# Blinker.net
KiCad netlist of a schematic drawn in Altium Designer
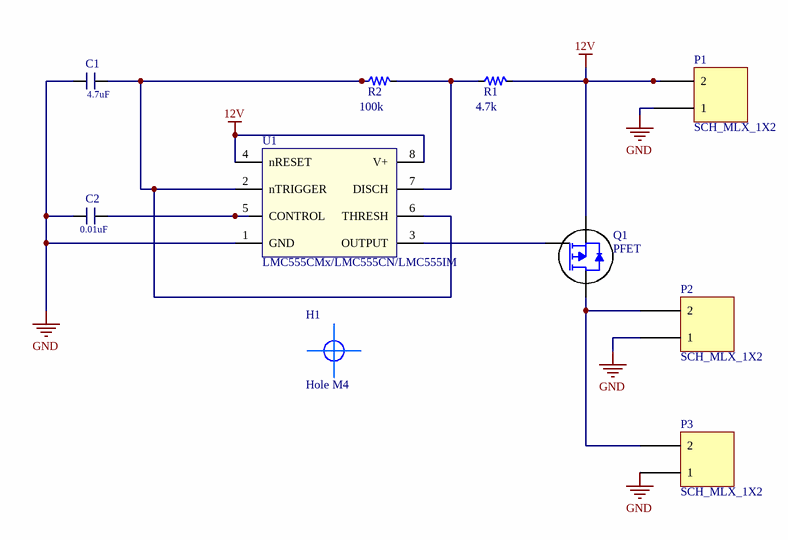
[diagram p0: Blinker.SchDoc]

(export (version "E")
  (design (tool "Eeschema 10.0.6"))
  (components
    (comp (ref "C1")
      (value "SCH_GENERIC_CAPACITOR_0603")
      (footprint "PCB_GENERIC_SMD_0603")
      (description "Generic SMD capacitor 0603")
      (fields (field (name "TOLERANCE") "*%") (field (name "CAPACITANCE") "4.7uF"))
      (libsource (lib "Generic 0603 Capacitor") (part "SCH_GENERIC_CAPACITOR_0603"))
    )
    (comp (ref "C2")
      (value "SCH_GENERIC_CAPACITOR_0603")
      (footprint "PCB_GENERIC_SMD_0603")
      (description "Generic SMD capacitor 0603")
      (fields (field (name "TOLERANCE") "*%") (field (name "CAPACITANCE") "0.01uF"))
      (libsource (lib "Generic 0603 Capacitor") (part "SCH_GENERIC_CAPACITOR_0603"))
    )
    (comp (ref "H1") (value "Hole M4") (footprint "#10Hole") (libsource (lib "#10Hole") (part "#10Hole")))
    (comp (ref "P1")
      (value "SCH_MLX_1X2")
      (footprint "PCB_MLX_MICROFIT_1X2")
      (libsource (lib "Molex Microfit 3.0 1x2") (part "SCH_MLX_1X2"))
    )
    (comp (ref "P2")
      (value "SCH_MLX_1X2")
      (footprint "PCB_MLX_MICROFIT_1X2")
      (libsource (lib "Molex Microfit 3.0 1x2") (part "SCH_MLX_1X2"))
    )
    (comp (ref "P3")
      (value "SCH_MLX_1X2")
      (footprint "PCB_MLX_MICROFIT_1X2")
      (libsource (lib "Molex Microfit 3.0 1x2") (part "SCH_MLX_1X2"))
    )
    (comp (ref "Q1")
      (value "PFET")
      (footprint "SOT23F")
      (description "MOSFET P CH 30V 6A 2-3Z1A")
      (libsource (lib "Blinker") (part "PFET"))
    )
    (comp (ref "R1")
      (value "SCH_GENERIC_RESISTOR_0603")
      (footprint "PCB_GENERIC_SMD_0603")
      (description "Generic SMD resistor 0603")
      (fields (field (name "RESISTANCE") "4.7k"))
      (libsource (lib "Generic 0603 Resistor") (part "SCH_GENERIC_RESISTOR_0603"))
    )
    (comp (ref "R2")
      (value "SCH_GENERIC_RESISTOR_0603")
      (footprint "PCB_GENERIC_SMD_0603")
      (description "Generic SMD resistor 0603")
      (fields (field (name "RESISTANCE") "100k"))
      (libsource (lib "Generic 0603 Resistor") (part "SCH_GENERIC_RESISTOR_0603"))
    )
    (comp (ref "U1")
      (value "LMC555CMx/LMC555CN/LMC555IM")
      (footprint "D-8")
      (description "555 Type, Timer/Oscillator (Single) IC 3MHz 8-SOIC")
      (fields (field (name "PART NUMBER") "LMC555CMX/NOPB") (field (name "MANUFACTURER") "Texas Instruments"))
      (libsource (lib "Blinker") (part "LMC555CMx/LMC555CN/LMC555IM"))
    )
  )
  (nets
    (net (code "1") (name "12V") (class "Default")
      (node (ref "P1") (pin "2") (pinfunction "2_2") (pintype "passive"))
      (node (ref "Q1") (pin "2") (pinfunction "S_2") (pintype "passive"))
      (node (ref "R1") (pin "2") (pinfunction "2_2") (pintype "passive"))
      (node (ref "U1") (pin "4") (pinfunction "nRESET_4") (pintype "passive"))
      (node (ref "U1") (pin "8") (pinfunction "V+_8") (pintype "passive"))
    )
    (net (code "2") (name "GND") (class "Default")
      (node (ref "C1") (pin "1") (pinfunction "1_1") (pintype "passive"))
      (node (ref "C2") (pin "1") (pinfunction "1_1") (pintype "passive"))
      (node (ref "P1") (pin "1") (pinfunction "1_1") (pintype "passive"))
      (node (ref "P2") (pin "1") (pinfunction "1_1") (pintype "passive"))
      (node (ref "P3") (pin "1") (pinfunction "1_1") (pintype "passive"))
      (node (ref "U1") (pin "1") (pinfunction "GND_1") (pintype "passive"))
    )
    (net (code "3") (name "Net-(Q1-D)") (class "Default")
      (node (ref "P2") (pin "2") (pinfunction "2_2") (pintype "passive"))
      (node (ref "P3") (pin "2") (pinfunction "2_2") (pintype "passive"))
      (node (ref "Q1") (pin "3") (pinfunction "D_3") (pintype "passive"))
    )
    (net (code "4") (name "Net-(Q1-G)") (class "Default")
      (node (ref "Q1") (pin "1") (pinfunction "G_1") (pintype "passive"))
      (node (ref "U1") (pin "3") (pinfunction "OUTPUT_3") (pintype "passive"))
    )
    (net (code "5") (name "Net-(U1-CONTROL)") (class "Default")
      (node (ref "C2") (pin "2") (pinfunction "2_2") (pintype "passive"))
      (node (ref "U1") (pin "5") (pinfunction "CONTROL_5") (pintype "passive"))
    )
    (net (code "6") (name "Net-(U1-DISCH)") (class "Default")
      (node (ref "R1") (pin "1") (pinfunction "1_1") (pintype "passive"))
      (node (ref "R2") (pin "2") (pinfunction "2_2") (pintype "passive"))
      (node (ref "U1") (pin "7") (pinfunction "DISCH_7") (pintype "passive"))
    )
    (net (code "7") (name "Net-(U1-THRESH)") (class "Default")
      (node (ref "C1") (pin "2") (pinfunction "2_2") (pintype "passive"))
      (node (ref "R2") (pin "1") (pinfunction "1_1") (pintype "passive"))
      (node (ref "U1") (pin "2") (pinfunction "nTRIGGER_2") (pintype "passive"))
      (node (ref "U1") (pin "6") (pinfunction "THRESH_6") (pintype "passive"))
    )
  )
)
